# SCH_St-Peters-Crest_2025-05-22.net
KiCad netlist of a schematic drawn in EasyEDA
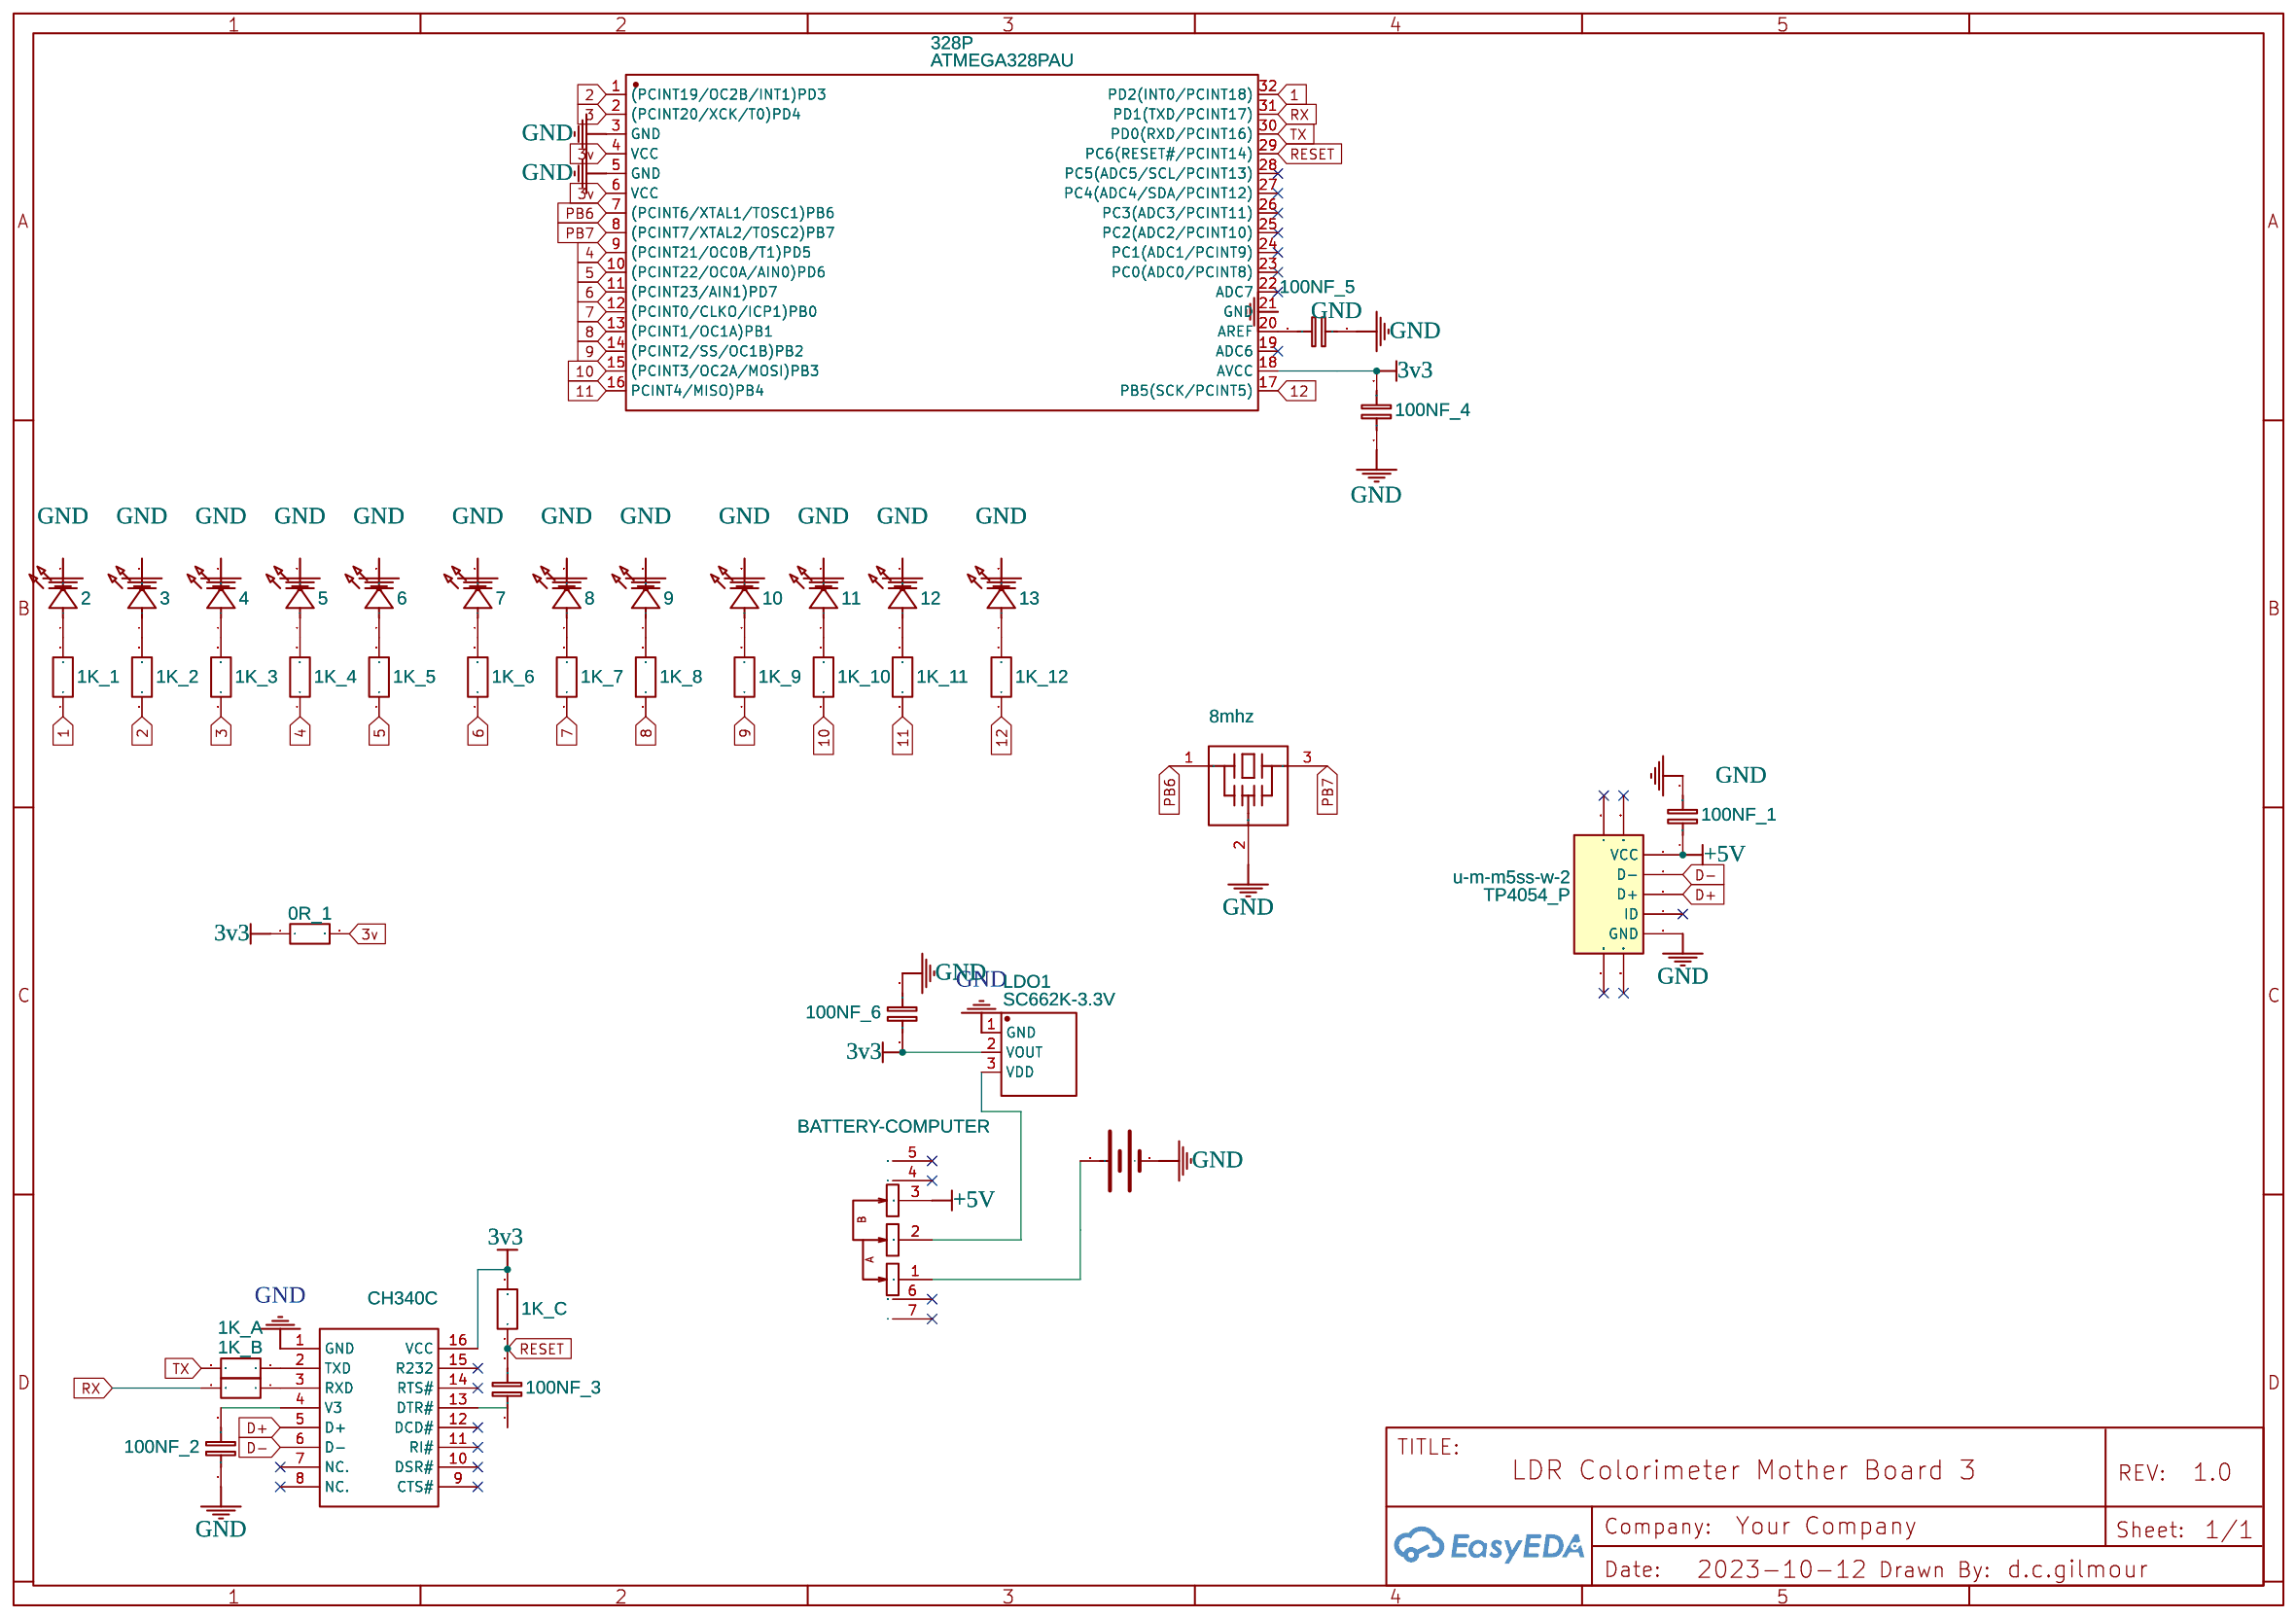
[diagram p0: schematic sheet]

(export (version "E")
  (design (tool "Eeschema 10.0.6"))
  (components
    (comp (ref "0R_1") (value "1k") (libsource (lib "") (part "R_0603_EU_1")))
    (comp (ref "1K_1") (value "1k") (libsource (lib "") (part "R_0603_EU")))
    (comp (ref "1K_2") (value "1k") (libsource (lib "") (part "R_0603_EU")))
    (comp (ref "1K_3") (value "1k") (libsource (lib "") (part "R_0603_EU")))
    (comp (ref "1K_4") (value "1k") (libsource (lib "") (part "R_0603_EU")))
    (comp (ref "1K_5") (value "1k") (libsource (lib "") (part "R_0603_EU")))
    (comp (ref "1K_6") (value "1k") (libsource (lib "") (part "R_0603_EU")))
    (comp (ref "1K_7") (value "1k") (libsource (lib "") (part "R_0603_EU")))
    (comp (ref "1K_8") (value "1k") (libsource (lib "") (part "R_0603_EU")))
    (comp (ref "1K_9") (value "1k") (libsource (lib "") (part "R_0603_EU")))
    (comp (ref "1K_10") (value "1k") (libsource (lib "") (part "R_0603_EU")))
    (comp (ref "1K_11") (value "1k") (libsource (lib "") (part "R_0603_EU")))
    (comp (ref "1K_12") (value "1k") (libsource (lib "") (part "R_0603_EU")))
    (comp (ref "1K_A") (value "1k") (libsource (lib "") (part "R_0603_EU_3")))
    (comp (ref "1K_B") (value "1k") (libsource (lib "") (part "R_0603_EU_2")))
    (comp (ref "1K_C") (value "1k") (libsource (lib "") (part "R_0603_EU_4")))
    (comp (ref "2")
      (value "XL-3216SURC")
      (fields (field (name "Manufacturer") "XINGLIGHT(成兴光)"))
      (libsource (lib "") (part "XL-3216SURC"))
    )
    (comp (ref "3")
      (value "XL-3216SURC")
      (fields (field (name "Manufacturer") "XINGLIGHT(成兴光)"))
      (libsource (lib "") (part "XL-3216SURC"))
    )
    (comp (ref "4")
      (value "XL-3216SURC")
      (fields (field (name "Manufacturer") "XINGLIGHT(成兴光)"))
      (libsource (lib "") (part "XL-3216SURC"))
    )
    (comp (ref "5")
      (value "XL-3216SURC")
      (fields (field (name "Manufacturer") "XINGLIGHT(成兴光)"))
      (libsource (lib "") (part "XL-3216SURC"))
    )
    (comp (ref "6")
      (value "XL-3216SURC")
      (fields (field (name "Manufacturer") "XINGLIGHT(成兴光)"))
      (libsource (lib "") (part "XL-3216SURC"))
    )
    (comp (ref "7")
      (value "XL-3216SURC")
      (fields (field (name "Manufacturer") "XINGLIGHT(成兴光)"))
      (libsource (lib "") (part "XL-3216SURC"))
    )
    (comp (ref "8")
      (value "XL-3216SURC")
      (fields (field (name "Manufacturer") "XINGLIGHT(成兴光)"))
      (libsource (lib "") (part "XL-3216SURC"))
    )
    (comp (ref "9")
      (value "XL-3216SURC")
      (fields (field (name "Manufacturer") "XINGLIGHT(成兴光)"))
      (libsource (lib "") (part "XL-3216SURC"))
    )
    (comp (ref "10")
      (value "XL-3216SURC")
      (fields (field (name "Manufacturer") "XINGLIGHT(成兴光)"))
      (libsource (lib "") (part "XL-3216SURC"))
    )
    (comp (ref "11")
      (value "XL-3216SURC")
      (fields (field (name "Manufacturer") "XINGLIGHT(成兴光)"))
      (libsource (lib "") (part "XL-3216SURC"))
    )
    (comp (ref "12")
      (value "XL-3216SURC")
      (fields (field (name "Manufacturer") "XINGLIGHT(成兴光)"))
      (libsource (lib "") (part "XL-3216SURC"))
    )
    (comp (ref "13")
      (value "XL-3216SURC")
      (fields (field (name "Manufacturer") "XINGLIGHT(成兴光)"))
      (libsource (lib "") (part "XL-3216SURC"))
    )
    (comp (ref "16MHZ")
      (value "8mhz")
      (fields
        (field (name "Manufacturer Part") "CSTCE16M0V13C99-R0")
        (field (name "Manufacturer") "muRata(村田)")
      )
      (libsource (lib "") (part "CSTCE16M0V13C99-R0"))
    )
    (comp (ref "100NF_1") (value "0.1u") (libsource (lib "") (part "C_0603_EU_2")))
    (comp (ref "100NF_2") (value "0.1u") (libsource (lib "") (part "C_0603_EU")))
    (comp (ref "100NF_3") (value "0.1u") (libsource (lib "") (part "C_0603_EU_4")))
    (comp (ref "100NF_4") (value "0.1u") (libsource (lib "") (part "C_0603_EU")))
    (comp (ref "100NF_5") (value "0.1u") (libsource (lib "") (part "C_0603_EU_1")))
    (comp (ref "100NF_6") (value "0.1u") (libsource (lib "") (part "C_0603_EU_3")))
    (comp (ref "328P")
      (value "ATMEGA328PAU")
      (fields (field (name "Manufacturer Part") "Atmega328pAU"))
      (libsource (lib "") (part "ATMEGA328PAU"))
    )
    (comp (ref "BATTERY-COMPUTER")
      (value "MK-12C02-G015_C9900021215")
      (fields (field (name "Manufacturer Part") "MK-12C02-G015"))
      (libsource (lib "") (part "MK-12C02-G015_C9900021215"))
    )
    (comp (ref "CH340C")
      (value "CH340C")
      (fields (field (name "Manufacturer") "WCH(南京沁恒)"))
      (libsource (lib "") (part "CH340C"))
    )
    (comp (ref "LDO1")
      (value "SC662K-3.3V")
      (fields (field (name "Manufacturer") "FM"))
      (libsource (lib "") (part "SC662K-3.3V"))
    )
    (comp (ref "TP4054_P")
      (value "u-m-m5ss-w-2")
      (fields (field (name "Manufacturer Part") "U-M-M5SS-W-2") (field (name "Manufacturer") "韩国韩荣"))
      (libsource (lib "") (part "u-m-m5ss-w-2"))
    )
    (comp (ref "U1") (value "CR2032-卧式贴片") (libsource (lib "") (part "CR2032-卧式贴片")))
  )
  (nets
    (net (code "1") (name "+5V") (class "Default")
      (node (ref "100NF_1") (pin "1") (pinfunction "1_1") (pintype "unspecified"))
      (node (ref "BATTERY-COMPUTER") (pin "3") (pinfunction "3_3") (pintype "unspecified"))
      (node (ref "TP4054_P") (pin "1") (pinfunction "VCC_1") (pintype "input"))
    )
    (net (code "2") (name "1") (class "Default")
      (node (ref "1K_1") (pin "1") (pinfunction "1_1") (pintype "unspecified"))
      (node (ref "328P") (pin "32") (pinfunction "PD2(INT0/PCINT18)_32") (pintype "unspecified"))
    )
    (net (code "3") (name "2") (class "Default")
      (node (ref "1K_2") (pin "1") (pinfunction "1_1") (pintype "unspecified"))
      (node (ref "328P") (pin "1") (pinfunction "(PCINT19/OC2B/INT1)PD3_1") (pintype "unspecified"))
    )
    (net (code "4") (name "3") (class "Default")
      (node (ref "1K_3") (pin "1") (pinfunction "1_1") (pintype "unspecified"))
      (node (ref "328P") (pin "2") (pinfunction "(PCINT20/XCK/T0)PD4_2") (pintype "unspecified"))
    )
    (net (code "5") (name "3v") (class "Default")
      (node (ref "0R_1") (pin "2") (pinfunction "2_2") (pintype "unspecified"))
      (node (ref "328P") (pin "4") (pinfunction "VCC_4") (pintype "unspecified"))
      (node (ref "328P") (pin "6") (pinfunction "VCC_6") (pintype "unspecified"))
    )
    (net (code "6") (name "3v3") (class "Default")
      (node (ref "0R_1") (pin "1") (pinfunction "1_1") (pintype "unspecified"))
      (node (ref "100NF_4") (pin "2") (pinfunction "2_2") (pintype "unspecified"))
      (node (ref "100NF_6") (pin "1") (pinfunction "1_1") (pintype "unspecified"))
      (node (ref "1K_C") (pin "2") (pinfunction "2_2") (pintype "unspecified"))
      (node (ref "328P") (pin "18") (pinfunction "AVCC_18") (pintype "unspecified"))
      (node (ref "CH340C") (pin "16") (pinfunction "VCC_16") (pintype "unspecified"))
      (node (ref "LDO1") (pin "2") (pinfunction "VOUT_2") (pintype "unspecified"))
    )
    (net (code "7") (name "4") (class "Default")
      (node (ref "1K_4") (pin "1") (pinfunction "1_1") (pintype "unspecified"))
      (node (ref "328P") (pin "9") (pinfunction "(PCINT21/OC0B/T1)PD5_9") (pintype "unspecified"))
    )
    (net (code "8") (name "5") (class "Default")
      (node (ref "1K_5") (pin "1") (pinfunction "1_1") (pintype "unspecified"))
      (node (ref "328P") (pin "10") (pinfunction "(PCINT22/OC0A/AIN0)PD6_10") (pintype "unspecified"))
    )
    (net (code "9") (name "6") (class "Default")
      (node (ref "1K_6") (pin "1") (pinfunction "1_1") (pintype "unspecified"))
      (node (ref "328P") (pin "11") (pinfunction "(PCINT23/AIN1)PD7_11") (pintype "unspecified"))
    )
    (net (code "10") (name "7") (class "Default")
      (node (ref "1K_7") (pin "1") (pinfunction "1_1") (pintype "unspecified"))
      (node (ref "328P") (pin "12") (pinfunction "(PCINT0/CLKO/ICP1)PB0_12") (pintype "unspecified"))
    )
    (net (code "11") (name "8") (class "Default")
      (node (ref "1K_8") (pin "1") (pinfunction "1_1") (pintype "unspecified"))
      (node (ref "328P") (pin "13") (pinfunction "(PCINT1/OC1A)PB1_13") (pintype "unspecified"))
    )
    (net (code "12") (name "9") (class "Default")
      (node (ref "1K_9") (pin "1") (pinfunction "1_1") (pintype "unspecified"))
      (node (ref "328P") (pin "14") (pinfunction "(PCINT2/SS/OC1B)PB2_14") (pintype "unspecified"))
    )
    (net (code "13") (name "10") (class "Default")
      (node (ref "1K_10") (pin "1") (pinfunction "1_1") (pintype "unspecified"))
      (node (ref "328P") (pin "15") (pinfunction "(PCINT3/OC2A/MOSI)PB3_15") (pintype "unspecified"))
    )
    (net (code "14") (name "11") (class "Default")
      (node (ref "1K_11") (pin "1") (pinfunction "1_1") (pintype "unspecified"))
      (node (ref "328P") (pin "16") (pinfunction "PCINT4/MISO)PB4_16") (pintype "unspecified"))
    )
    (net (code "15") (name "12") (class "Default")
      (node (ref "1K_12") (pin "1") (pinfunction "1_1") (pintype "unspecified"))
      (node (ref "328P") (pin "17") (pinfunction "PB5(SCK/PCINT5)_17") (pintype "unspecified"))
    )
    (net (code "16") (name "D+") (class "Default")
      (node (ref "CH340C") (pin "5") (pinfunction "D+_5") (pintype "unspecified"))
      (node (ref "TP4054_P") (pin "3") (pinfunction "D+_3") (pintype "input"))
    )
    (net (code "17") (name "D-") (class "Default")
      (node (ref "CH340C") (pin "6") (pinfunction "D-_6") (pintype "unspecified"))
      (node (ref "TP4054_P") (pin "2") (pinfunction "D-_2") (pintype "input"))
    )
    (net (code "18") (name "GND") (class "Default")
      (node (ref "10") (pin "2") (pinfunction "A_2") (pintype "unspecified"))
      (node (ref "100NF_1") (pin "2") (pinfunction "2_2") (pintype "unspecified"))
      (node (ref "100NF_2") (pin "1") (pinfunction "1_1") (pintype "unspecified"))
      (node (ref "100NF_4") (pin "1") (pinfunction "1_1") (pintype "unspecified"))
      (node (ref "100NF_5") (pin "1") (pinfunction "1_1") (pintype "unspecified"))
      (node (ref "100NF_6") (pin "2") (pinfunction "2_2") (pintype "unspecified"))
      (node (ref "11") (pin "2") (pinfunction "A_2") (pintype "unspecified"))
      (node (ref "12") (pin "2") (pinfunction "A_2") (pintype "unspecified"))
      (node (ref "13") (pin "2") (pinfunction "A_2") (pintype "unspecified"))
      (node (ref "16MHZ") (pin "2") (pinfunction "VSS_2") (pintype "passive"))
      (node (ref "2") (pin "2") (pinfunction "A_2") (pintype "unspecified"))
      (node (ref "3") (pin "2") (pinfunction "A_2") (pintype "unspecified"))
      (node (ref "328P") (pin "21") (pinfunction "GND_21") (pintype "unspecified"))
      (node (ref "328P") (pin "3") (pinfunction "GND_3") (pintype "unspecified"))
      (node (ref "328P") (pin "5") (pinfunction "GND_5") (pintype "unspecified"))
      (node (ref "4") (pin "2") (pinfunction "A_2") (pintype "unspecified"))
      (node (ref "5") (pin "2") (pinfunction "A_2") (pintype "unspecified"))
      (node (ref "6") (pin "2") (pinfunction "A_2") (pintype "unspecified"))
      (node (ref "7") (pin "2") (pinfunction "A_2") (pintype "unspecified"))
      (node (ref "8") (pin "2") (pinfunction "A_2") (pintype "unspecified"))
      (node (ref "9") (pin "2") (pinfunction "A_2") (pintype "unspecified"))
      (node (ref "CH340C") (pin "1") (pinfunction "GND_1") (pintype "unspecified"))
      (node (ref "LDO1") (pin "1") (pinfunction "GND_1") (pintype "unspecified"))
      (node (ref "TP4054_P") (pin "5") (pinfunction "GND_5") (pintype "input"))
      (node (ref "U1") (pin "1") (pinfunction "-_1") (pintype "passive"))
    )
    (net (code "19") (name "Net-(2-K)") (class "Default")
      (node (ref "1K_1") (pin "2") (pinfunction "2_2") (pintype "unspecified"))
      (node (ref "2") (pin "1") (pinfunction "K_1") (pintype "unspecified"))
    )
    (net (code "20") (name "Net-(3-K)") (class "Default")
      (node (ref "1K_2") (pin "2") (pinfunction "2_2") (pintype "unspecified"))
      (node (ref "3") (pin "1") (pinfunction "K_1") (pintype "unspecified"))
    )
    (net (code "21") (name "Net-(4-K)") (class "Default")
      (node (ref "1K_3") (pin "2") (pinfunction "2_2") (pintype "unspecified"))
      (node (ref "4") (pin "1") (pinfunction "K_1") (pintype "unspecified"))
    )
    (net (code "22") (name "Net-(5-K)") (class "Default")
      (node (ref "1K_4") (pin "2") (pinfunction "2_2") (pintype "unspecified"))
      (node (ref "5") (pin "1") (pinfunction "K_1") (pintype "unspecified"))
    )
    (net (code "23") (name "Net-(6-K)") (class "Default")
      (node (ref "1K_5") (pin "2") (pinfunction "2_2") (pintype "unspecified"))
      (node (ref "6") (pin "1") (pinfunction "K_1") (pintype "unspecified"))
    )
    (net (code "24") (name "Net-(7-K)") (class "Default")
      (node (ref "1K_6") (pin "2") (pinfunction "2_2") (pintype "unspecified"))
      (node (ref "7") (pin "1") (pinfunction "K_1") (pintype "unspecified"))
    )
    (net (code "25") (name "Net-(8-K)") (class "Default")
      (node (ref "1K_7") (pin "2") (pinfunction "2_2") (pintype "unspecified"))
      (node (ref "8") (pin "1") (pinfunction "K_1") (pintype "unspecified"))
    )
    (net (code "26") (name "Net-(9-K)") (class "Default")
      (node (ref "1K_8") (pin "2") (pinfunction "2_2") (pintype "unspecified"))
      (node (ref "9") (pin "1") (pinfunction "K_1") (pintype "unspecified"))
    )
    (net (code "27") (name "Net-(10-K)") (class "Default")
      (node (ref "10") (pin "1") (pinfunction "K_1") (pintype "unspecified"))
      (node (ref "1K_9") (pin "2") (pinfunction "2_2") (pintype "unspecified"))
    )
    (net (code "28") (name "Net-(11-K)") (class "Default")
      (node (ref "11") (pin "1") (pinfunction "K_1") (pintype "unspecified"))
      (node (ref "1K_10") (pin "2") (pinfunction "2_2") (pintype "unspecified"))
    )
    (net (code "29") (name "Net-(12-K)") (class "Default")
      (node (ref "12") (pin "1") (pinfunction "K_1") (pintype "unspecified"))
      (node (ref "1K_11") (pin "2") (pinfunction "2_2") (pintype "unspecified"))
    )
    (net (code "30") (name "Net-(13-K)") (class "Default")
      (node (ref "13") (pin "1") (pinfunction "K_1") (pintype "unspecified"))
      (node (ref "1K_12") (pin "2") (pinfunction "2_2") (pintype "unspecified"))
    )
    (net (code "31") (name "Net-(328P-AREF)") (class "Default")
      (node (ref "100NF_5") (pin "2") (pinfunction "2_2") (pintype "unspecified"))
      (node (ref "328P") (pin "20") (pinfunction "AREF_20") (pintype "unspecified"))
    )
    (net (code "32") (name "Net-(CH340C-DTR#)") (class "Default")
      (node (ref "100NF_3") (pin "1") (pinfunction "1_1") (pintype "unspecified"))
      (node (ref "CH340C") (pin "13") (pinfunction "DTR#_13") (pintype "unspecified"))
    )
    (net (code "33") (name "Net-(CH340C-RXD)") (class "Default")
      (node (ref "1K_B") (pin "1") (pinfunction "1_1") (pintype "unspecified"))
      (node (ref "CH340C") (pin "3") (pinfunction "RXD_3") (pintype "unspecified"))
    )
    (net (code "34") (name "Net-(CH340C-TXD)") (class "Default")
      (node (ref "1K_A") (pin "1") (pinfunction "1_1") (pintype "unspecified"))
      (node (ref "CH340C") (pin "2") (pinfunction "TXD_2") (pintype "unspecified"))
    )
    (net (code "35") (name "Net-(CH340C-V3)") (class "Default")
      (node (ref "100NF_2") (pin "2") (pinfunction "2_2") (pintype "unspecified"))
      (node (ref "CH340C") (pin "4") (pinfunction "V3_4") (pintype "unspecified"))
    )
    (net (code "36") (name "Net-(LDO1-VDD)") (class "Default")
      (node (ref "BATTERY-COMPUTER") (pin "2") (pinfunction "2_2") (pintype "unspecified"))
      (node (ref "LDO1") (pin "3") (pinfunction "VDD_3") (pintype "unspecified"))
    )
    (net (code "37") (name "Net-(U1-+)") (class "Default")
      (node (ref "BATTERY-COMPUTER") (pin "1") (pinfunction "1_1") (pintype "unspecified"))
      (node (ref "U1") (pin "2") (pinfunction "+_2") (pintype "passive"))
    )
    (net (code "38") (name "PB6") (class "Default")
      (node (ref "16MHZ") (pin "1") (pinfunction "1_1") (pintype "output"))
      (node (ref "328P") (pin "7") (pinfunction "(PCINT6/XTAL1/TOSC1)PB6_7") (pintype "unspecified"))
    )
    (net (code "39") (name "PB7") (class "Default")
      (node (ref "16MHZ") (pin "3") (pinfunction "3_3") (pintype "input"))
      (node (ref "328P") (pin "8") (pinfunction "(PCINT7/XTAL2/TOSC2)PB7_8") (pintype "unspecified"))
    )
    (net (code "40") (name "RESET") (class "Default")
      (node (ref "100NF_3") (pin "2") (pinfunction "2_2") (pintype "unspecified"))
      (node (ref "1K_C") (pin "1") (pinfunction "1_1") (pintype "unspecified"))
      (node (ref "328P") (pin "29") (pinfunction "PC6(RESET#/PCINT14)_29") (pintype "unspecified"))
    )
    (net (code "41") (name "RX") (class "Default")
      (node (ref "1K_B") (pin "2") (pinfunction "2_2") (pintype "unspecified"))
      (node (ref "328P") (pin "31") (pinfunction "PD1(TXD/PCINT17)_31") (pintype "unspecified"))
    )
    (net (code "42") (name "TX") (class "Default")
      (node (ref "1K_A") (pin "2") (pinfunction "2_2") (pintype "unspecified"))
      (node (ref "328P") (pin "30") (pinfunction "PD0(RXD/PCINT16)_30") (pintype "unspecified"))
    )
    (net (code "43") (name "unconnected-(328P-ADC6-Pad19)") (class "Default")
      (node (ref "328P") (pin "19") (pinfunction "ADC6_19") (pintype "unspecified+no_connect"))
    )
    (net (code "44") (name "unconnected-(328P-ADC7-Pad22)") (class "Default")
      (node (ref "328P") (pin "22") (pinfunction "ADC7_22") (pintype "unspecified+no_connect"))
    )
    (net (code "45") (name "unconnected-(328P-PC0(ADC0{slash}PCINT8)-Pad23)") (class "Default")
      (node (ref "328P") (pin "23") (pinfunction "PC0(ADC0/PCINT8)_23") (pintype "unspecified+no_connect"))
    )
    (net (code "46") (name "unconnected-(328P-PC1(ADC1{slash}PCINT9)-Pad24)") (class "Default")
      (node (ref "328P") (pin "24") (pinfunction "PC1(ADC1/PCINT9)_24") (pintype "unspecified+no_connect"))
    )
    (net (code "47") (name "unconnected-(328P-PC2(ADC2{slash}PCINT10)-Pad25)") (class "Default")
      (node (ref "328P") (pin "25") (pinfunction "PC2(ADC2/PCINT10)_25") (pintype "unspecified+no_connect"))
    )
    (net (code "48") (name "unconnected-(328P-PC3(ADC3{slash}PCINT11)-Pad26)") (class "Default")
      (node (ref "328P") (pin "26") (pinfunction "PC3(ADC3/PCINT11)_26") (pintype "unspecified+no_connect"))
    )
    (net (code "49") (name "unconnected-(328P-PC4(ADC4{slash}SDA{slash}PCINT12)-Pad27)") (class "Default")
      (node (ref "328P") (pin "27") (pinfunction "PC4(ADC4/SDA/PCINT12)_27") (pintype "unspecified+no_connect"))
    )
    (net (code "50") (name "unconnected-(328P-PC5(ADC5{slash}SCL{slash}PCINT13)-Pad28)") (class "Default")
      (node (ref "328P") (pin "28") (pinfunction "PC5(ADC5/SCL/PCINT13)_28") (pintype "unspecified+no_connect"))
    )
    (net (code "51") (name "unconnected-(BATTERY-COMPUTER-Pad4)") (class "Default")
      (node (ref "BATTERY-COMPUTER") (pin "4") (pinfunction "4_4") (pintype "unspecified+no_connect"))
    )
    (net (code "52") (name "unconnected-(BATTERY-COMPUTER-Pad5)") (class "Default")
      (node (ref "BATTERY-COMPUTER") (pin "5") (pinfunction "5_5") (pintype "unspecified+no_connect"))
    )
    (net (code "53") (name "unconnected-(BATTERY-COMPUTER-Pad6)") (class "Default")
      (node (ref "BATTERY-COMPUTER") (pin "6") (pinfunction "6_6") (pintype "unspecified+no_connect"))
    )
    (net (code "54") (name "unconnected-(BATTERY-COMPUTER-Pad7)") (class "Default")
      (node (ref "BATTERY-COMPUTER") (pin "7") (pinfunction "7_7") (pintype "unspecified+no_connect"))
    )
    (net (code "55") (name "unconnected-(CH340C-CTS#-Pad9)") (class "Default")
      (node (ref "CH340C") (pin "9") (pinfunction "CTS#_9") (pintype "unspecified+no_connect"))
    )
    (net (code "56") (name "unconnected-(CH340C-DCD#-Pad12)") (class "Default")
      (node (ref "CH340C") (pin "12") (pinfunction "DCD#_12") (pintype "unspecified+no_connect"))
    )
    (net (code "57") (name "unconnected-(CH340C-DSR#-Pad10)") (class "Default")
      (node (ref "CH340C") (pin "10") (pinfunction "DSR#_10") (pintype "unspecified+no_connect"))
    )
    (net (code "58") (name "unconnected-(CH340C-NC.-Pad7)") (class "Default")
      (node (ref "CH340C") (pin "7") (pinfunction "NC._7") (pintype "unspecified+no_connect"))
    )
    (net (code "59") (name "unconnected-(CH340C-NC.-Pad8)") (class "Default")
      (node (ref "CH340C") (pin "8") (pinfunction "NC._8") (pintype "unspecified+no_connect"))
    )
    (net (code "60") (name "unconnected-(CH340C-R232-Pad15)") (class "Default")
      (node (ref "CH340C") (pin "15") (pinfunction "R232_15") (pintype "unspecified+no_connect"))
    )
    (net (code "61") (name "unconnected-(CH340C-RI#-Pad11)") (class "Default")
      (node (ref "CH340C") (pin "11") (pinfunction "RI#_11") (pintype "unspecified+no_connect"))
    )
    (net (code "62") (name "unconnected-(CH340C-RTS#-Pad14)") (class "Default")
      (node (ref "CH340C") (pin "14") (pinfunction "RTS#_14") (pintype "unspecified+no_connect"))
    )
    (net (code "63") (name "unconnected-(TP4054_P-ID-Pad4)") (class "Default")
      (node (ref "TP4054_P") (pin "4") (pinfunction "ID_4") (pintype "input+no_connect"))
    )
    (net (code "64") (name "unconnected-(TP4054_P-SHLD-Pad0)") (class "Default")
      (node (ref "TP4054_P") (pin "0") (pinfunction "SHLD_0") (pintype "unspecified+no_connect"))
    )
    (net (code "65") (name "unconnected-(TP4054_P-SHLD-Pad0)_1") (class "Default")
      (node (ref "TP4054_P") (pin "0") (pinfunction "SHLD_0") (pintype "unspecified+no_connect"))
    )
    (net (code "66") (name "unconnected-(TP4054_P-SHLD-Pad0)_2") (class "Default")
      (node (ref "TP4054_P") (pin "0") (pinfunction "SHLD_0") (pintype "unspecified+no_connect"))
    )
    (net (code "67") (name "unconnected-(TP4054_P-SHLD-Pad0)_3") (class "Default")
      (node (ref "TP4054_P") (pin "0") (pinfunction "SHLD_0") (pintype "unspecified+no_connect"))
    )
  )
)
